# MotorShield.net
KiCad netlist of a schematic drawn in Altium Designer
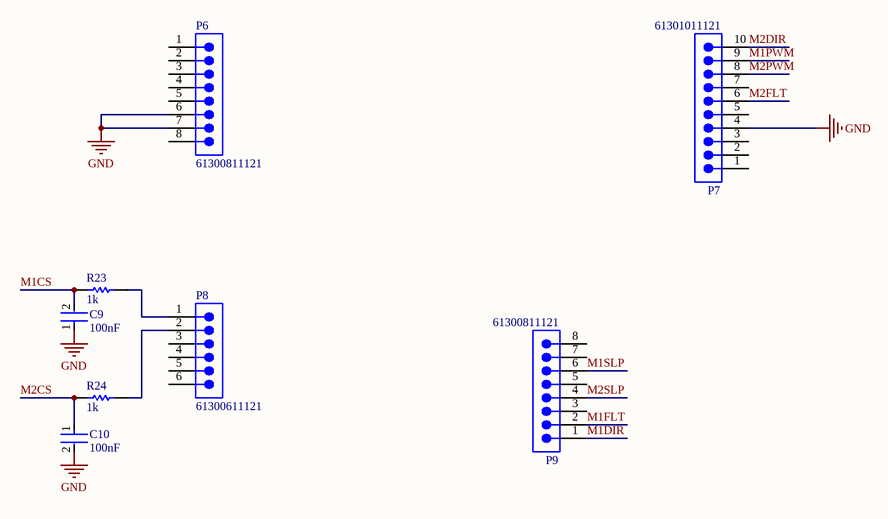
[diagram p0: MotorShield.SchDoc]

(export (version "E")
  (design (tool "Eeschema 10.0.6"))
  (components
    (comp (ref "C9")
      (value "100nF")
      (footprint "FP-0402B104K160CT-IPC_C")
      (description "CAP CER 0.1UF 16V X7R 0402")
      (fields (field (name "TOLERANCE") "10%"))
      (libsource (lib "Altium Content Vault") (part "b4654b650e69147ec39a6b967a45e02"))
    )
    (comp (ref "C10")
      (value "100nF")
      (footprint "FP-0402B104K160CT-IPC_C")
      (description "CAP CER 0.1UF 16V X7R 0402")
      (fields (field (name "TOLERANCE") "10%"))
      (libsource (lib "Altium Content Vault") (part "b4654b650e69147ec39a6b967a45e02"))
    )
    (comp (ref "P6")
      (value "61300811121")
      (footprint "61300811121")
      (description "THT Vertical Pin Header WR-PHD, Pitch 2.54 mm, Single Row, 8 pins")
      (libsource (lib "Altium Content Vault") (part "Header_Male_1R_08P"))
    )
    (comp (ref "P7")
      (value "61301011121")
      (footprint "61301011121")
      (description "THT Vertical Pin Header WR-PHD, Pitch 2.54 mm, Single Row, 10 pins")
      (libsource (lib "Altium Content Vault") (part "Header_Male_1R_10P"))
    )
    (comp (ref "P8")
      (value "61300611121")
      (footprint "61300611121")
      (description "THT Vertical Pin Header WR-PHD, Pitch 2.54 mm, Single Row, 6 pins")
      (libsource (lib "Altium Content Vault") (part "Header_Male_1R_06P"))
    )
    (comp (ref "P9")
      (value "61300811121")
      (footprint "61300811121")
      (description "THT Vertical Pin Header WR-PHD, Pitch 2.54 mm, Single Row, 8 pins")
      (libsource (lib "Altium Content Vault") (part "Header_Male_1R_08P"))
    )
    (comp (ref "R23")
      (value "1k")
      (footprint "RESC1005X40X25NL05T05")
      (description "Chip Resistor, 1 KOhm, +/- 1%, 100 mW, -55 to 155 degC, 0402 (1005 Metric), RoHS, Tape and Reel")
      (fields (field (name "PARTNUMBER") "ERJ-2RKF1001X") (field (name "MANUFACTURER") "Basic Passives"))
      (libsource (lib "Altium Content Vault") (part "RES-2"))
    )
    (comp (ref "R24")
      (value "1k")
      (footprint "RESC1005X40X25NL05T05")
      (description "Chip Resistor, 1 KOhm, +/- 1%, 100 mW, -55 to 155 degC, 0402 (1005 Metric), RoHS, Tape and Reel")
      (fields (field (name "PARTNUMBER") "ERJ-2RKF1001X") (field (name "MANUFACTURER") "Basic Passives"))
      (libsource (lib "Altium Content Vault") (part "RES-2"))
    )
  )
  (nets
    (net (code "1") (name "/M1CS") (class "Default")
      (node (ref "C9") (pin "2") (pinfunction "2_2") (pintype "passive"))
      (node (ref "R23") (pin "1") (pinfunction "1_1") (pintype "passive"))
    )
    (net (code "2") (name "/M1DIR") (class "Default")
      (node (ref "P9") (pin "1") (pinfunction "1_1") (pintype "passive"))
    )
    (net (code "3") (name "/M1FLT") (class "Default")
      (node (ref "P9") (pin "2") (pinfunction "2_2") (pintype "passive"))
    )
    (net (code "4") (name "/M1PWM") (class "Default")
      (node (ref "P7") (pin "9") (pinfunction "9_9") (pintype "passive"))
    )
    (net (code "5") (name "/M1SLP") (class "Default")
      (node (ref "P9") (pin "6") (pinfunction "6_6") (pintype "passive"))
    )
    (net (code "6") (name "/M2CS") (class "Default")
      (node (ref "C10") (pin "1") (pinfunction "1_1") (pintype "passive"))
      (node (ref "R24") (pin "1") (pinfunction "1_1") (pintype "passive"))
    )
    (net (code "7") (name "/M2DIR") (class "Default")
      (node (ref "P7") (pin "10") (pinfunction "10_10") (pintype "passive"))
    )
    (net (code "8") (name "/M2FLT") (class "Default")
      (node (ref "P7") (pin "6") (pinfunction "6_6") (pintype "passive"))
    )
    (net (code "9") (name "/M2PWM") (class "Default")
      (node (ref "P7") (pin "8") (pinfunction "8_8") (pintype "passive"))
    )
    (net (code "10") (name "/M2SLP") (class "Default")
      (node (ref "P9") (pin "4") (pinfunction "4_4") (pintype "passive"))
    )
    (net (code "11") (name "GND") (class "Default")
      (node (ref "C10") (pin "2") (pinfunction "2_2") (pintype "passive"))
      (node (ref "C9") (pin "1") (pinfunction "1_1") (pintype "passive"))
      (node (ref "P6") (pin "6") (pinfunction "6_6") (pintype "passive"))
      (node (ref "P6") (pin "7") (pinfunction "7_7") (pintype "passive"))
      (node (ref "P7") (pin "4") (pinfunction "4_4") (pintype "passive"))
    )
    (net (code "12") (name "Net-(P8-Pad1)") (class "Default")
      (node (ref "P8") (pin "1") (pinfunction "1_1") (pintype "passive"))
      (node (ref "R23") (pin "2") (pinfunction "2_2") (pintype "passive"))
    )
    (net (code "13") (name "Net-(P8-Pad2)") (class "Default")
      (node (ref "P8") (pin "2") (pinfunction "2_2") (pintype "passive"))
      (node (ref "R24") (pin "2") (pinfunction "2_2") (pintype "passive"))
    )
    (net (code "14") (name "unconnected-(P6-Pad1)") (class "Default")
      (node (ref "P6") (pin "1") (pinfunction "1_1") (pintype "passive"))
    )
    (net (code "15") (name "unconnected-(P6-Pad2)") (class "Default")
      (node (ref "P6") (pin "2") (pinfunction "2_2") (pintype "passive"))
    )
    (net (code "16") (name "unconnected-(P6-Pad3)") (class "Default")
      (node (ref "P6") (pin "3") (pinfunction "3_3") (pintype "passive"))
    )
    (net (code "17") (name "unconnected-(P6-Pad4)") (class "Default")
      (node (ref "P6") (pin "4") (pinfunction "4_4") (pintype "passive"))
    )
    (net (code "18") (name "unconnected-(P6-Pad5)") (class "Default")
      (node (ref "P6") (pin "5") (pinfunction "5_5") (pintype "passive"))
    )
    (net (code "19") (name "unconnected-(P6-Pad8)") (class "Default")
      (node (ref "P6") (pin "8") (pinfunction "8_8") (pintype "passive"))
    )
    (net (code "20") (name "unconnected-(P7-Pad1)") (class "Default")
      (node (ref "P7") (pin "1") (pinfunction "1_1") (pintype "passive"))
    )
    (net (code "21") (name "unconnected-(P7-Pad2)") (class "Default")
      (node (ref "P7") (pin "2") (pinfunction "2_2") (pintype "passive"))
    )
    (net (code "22") (name "unconnected-(P7-Pad3)") (class "Default")
      (node (ref "P7") (pin "3") (pinfunction "3_3") (pintype "passive"))
    )
    (net (code "23") (name "unconnected-(P7-Pad5)") (class "Default")
      (node (ref "P7") (pin "5") (pinfunction "5_5") (pintype "passive"))
    )
    (net (code "24") (name "unconnected-(P7-Pad7)") (class "Default")
      (node (ref "P7") (pin "7") (pinfunction "7_7") (pintype "passive"))
    )
    (net (code "25") (name "unconnected-(P8-Pad3)") (class "Default")
      (node (ref "P8") (pin "3") (pinfunction "3_3") (pintype "passive"))
    )
    (net (code "26") (name "unconnected-(P8-Pad4)") (class "Default")
      (node (ref "P8") (pin "4") (pinfunction "4_4") (pintype "passive"))
    )
    (net (code "27") (name "unconnected-(P8-Pad5)") (class "Default")
      (node (ref "P8") (pin "5") (pinfunction "5_5") (pintype "passive"))
    )
    (net (code "28") (name "unconnected-(P8-Pad6)") (class "Default")
      (node (ref "P8") (pin "6") (pinfunction "6_6") (pintype "passive"))
    )
    (net (code "29") (name "unconnected-(P9-Pad3)") (class "Default")
      (node (ref "P9") (pin "3") (pinfunction "3_3") (pintype "passive"))
    )
    (net (code "30") (name "unconnected-(P9-Pad5)") (class "Default")
      (node (ref "P9") (pin "5") (pinfunction "5_5") (pintype "passive"))
    )
    (net (code "31") (name "unconnected-(P9-Pad7)") (class "Default")
      (node (ref "P9") (pin "7") (pinfunction "7_7") (pintype "passive"))
    )
    (net (code "32") (name "unconnected-(P9-Pad8)") (class "Default")
      (node (ref "P9") (pin "8") (pinfunction "8_8") (pintype "passive"))
    )
  )
)
